# Motor_Driver.net
KiCad netlist of a schematic drawn in Altium Designer
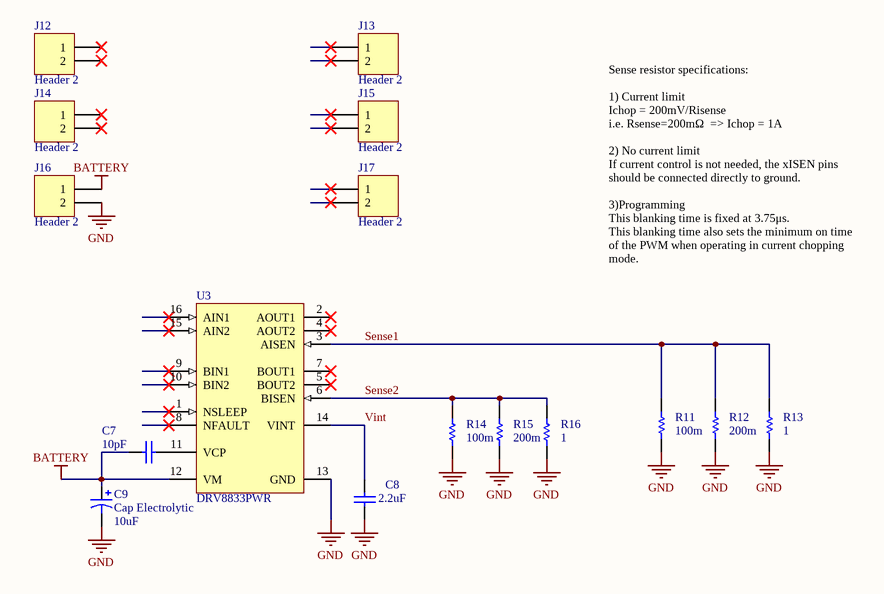
[diagram p0: Motor_Driver.SchDoc]

(export (version "E")
  (design (tool "Eeschema 10.0.6"))
  (components
    (comp (ref "C7")
      (value "10pF")
      (footprint "6-0805_M")
      (description "Capacitor")
      (fields (field (name "Comment") "cap") (field (name "PUBLISHER") "Altium Limited"))
      (libsource (lib "Miscellaneous Devices") (part "Cap"))
    )
    (comp (ref "C8")
      (value "2.2uF")
      (footprint "6-0805_M")
      (description "Capacitor")
      (fields (field (name "Comment") "cap") (field (name "PUBLISHER") "Altium Limited"))
      (libsource (lib "Miscellaneous Devices") (part "Cap"))
    )
    (comp (ref "C9")
      (value "Cap Electrolytic")
      (footprint "capacitor_3d")
      (description "Polarized Capacitor (Radial)")
      (fields (field (name "ALTIUM_VALUE") "10uF") (field (name "PUBLISHER") "Altium Limited"))
      (libsource (lib "Miscellaneous Devices") (part "Cap Pol1"))
    )
    (comp (ref "J12")
      (value "Header 2")
      (footprint "HDR1X2")
      (description "Header, 2-Pin")
      (fields (field (name "PUBLISHER") "Altium Limited"))
      (libsource (lib "") (part "Header 2_1"))
    )
    (comp (ref "J13")
      (value "Header 2")
      (footprint "HDR1X2")
      (description "Header, 2-Pin")
      (fields (field (name "PUBLISHER") "Altium Limited"))
      (libsource (lib "Miscellaneous Connectors") (part "Header 2"))
    )
    (comp (ref "J14")
      (value "Header 2")
      (footprint "HDR1X2")
      (description "Header, 2-Pin")
      (fields (field (name "PUBLISHER") "Altium Limited"))
      (libsource (lib "") (part "Header 2_1"))
    )
    (comp (ref "J15")
      (value "Header 2")
      (footprint "HDR1X2")
      (description "Header, 2-Pin")
      (fields (field (name "PUBLISHER") "Altium Limited"))
      (libsource (lib "Miscellaneous Connectors") (part "Header 2"))
    )
    (comp (ref "J16")
      (value "Header 2")
      (footprint "HDR1X2")
      (description "Header, 2-Pin")
      (fields (field (name "PUBLISHER") "Altium Limited"))
      (libsource (lib "") (part "Header 2_1"))
    )
    (comp (ref "J17")
      (value "Header 2")
      (footprint "HDR1X2")
      (description "Header, 2-Pin")
      (fields (field (name "PUBLISHER") "Altium Limited"))
      (libsource (lib "Miscellaneous Connectors") (part "Header 2"))
    )
    (comp (ref "R11")
      (value "100m")
      (footprint "6-0805_M")
      (description "Resistor")
      (fields (field (name "Comment") "Res1") (field (name "PUBLISHER") "Altium Limited"))
      (libsource (lib "Miscellaneous Devices") (part "Res1"))
    )
    (comp (ref "R12")
      (value "200m")
      (footprint "6-0805_M")
      (description "Resistor")
      (fields (field (name "Comment") "Res1") (field (name "PUBLISHER") "Altium Limited"))
      (libsource (lib "Miscellaneous Devices") (part "Res1"))
    )
    (comp (ref "R13")
      (value "1")
      (footprint "6-0805_M")
      (description "Resistor")
      (fields (field (name "Comment") "Res1") (field (name "PUBLISHER") "Altium Limited"))
      (libsource (lib "Miscellaneous Devices") (part "Res1"))
    )
    (comp (ref "R14")
      (value "100m")
      (footprint "6-0805_M")
      (description "Resistor")
      (fields (field (name "Comment") "Res1") (field (name "PUBLISHER") "Altium Limited"))
      (libsource (lib "Miscellaneous Devices") (part "Res1"))
    )
    (comp (ref "R15")
      (value "200m")
      (footprint "6-0805_M")
      (description "Resistor")
      (fields (field (name "Comment") "Res1") (field (name "PUBLISHER") "Altium Limited"))
      (libsource (lib "Miscellaneous Devices") (part "Res1"))
    )
    (comp (ref "R16")
      (value "1")
      (footprint "6-0805_M")
      (description "Resistor")
      (fields (field (name "Comment") "Res1") (field (name "PUBLISHER") "Altium Limited"))
      (libsource (lib "Miscellaneous Devices") (part "Res1"))
    )
    (comp (ref "U3")
      (value "DRV8833PWR")
      (footprint "TI-PW16_M")
      (fields (field (name "MANUFACTURER") "Texas Instruments"))
      (libsource (lib "Altium Content Vault") (part "CMP-1529-00001-1"))
    )
  )
  (nets
    (net (code "1") (name "/Sense1") (class "Default")
      (node (ref "R11") (pin "2") (pinfunction "2_2") (pintype "passive"))
      (node (ref "R12") (pin "2") (pinfunction "2_2") (pintype "passive"))
      (node (ref "R13") (pin "2") (pinfunction "2_2") (pintype "passive"))
      (node (ref "U3") (pin "3") (pinfunction "AISEN_3") (pintype "input"))
    )
    (net (code "2") (name "/Sense2") (class "Default")
      (node (ref "R14") (pin "2") (pinfunction "2_2") (pintype "passive"))
      (node (ref "R15") (pin "2") (pinfunction "2_2") (pintype "passive"))
      (node (ref "R16") (pin "2") (pinfunction "2_2") (pintype "passive"))
      (node (ref "U3") (pin "6") (pinfunction "BISEN_6") (pintype "input"))
    )
    (net (code "3") (name "/Vint") (class "Default")
      (node (ref "C8") (pin "2") (pinfunction "2_2") (pintype "passive"))
      (node (ref "U3") (pin "14") (pinfunction "VINT_14") (pintype "passive"))
    )
    (net (code "4") (name "BATTERY") (class "Default")
      (node (ref "C7") (pin "2") (pinfunction "2_2") (pintype "passive"))
      (node (ref "C9") (pin "1") (pinfunction "1_1") (pintype "passive"))
      (node (ref "J16") (pin "1") (pinfunction "1_1") (pintype "passive"))
      (node (ref "U3") (pin "12") (pinfunction "VM_12") (pintype "power_in"))
    )
    (net (code "5") (name "GND") (class "Default")
      (node (ref "C8") (pin "1") (pinfunction "1_1") (pintype "passive"))
      (node (ref "C9") (pin "2") (pinfunction "2_2") (pintype "passive"))
      (node (ref "J16") (pin "2") (pinfunction "2_2") (pintype "passive"))
      (node (ref "R11") (pin "1") (pinfunction "1_1") (pintype "passive"))
      (node (ref "R12") (pin "1") (pinfunction "1_1") (pintype "passive"))
      (node (ref "R13") (pin "1") (pinfunction "1_1") (pintype "passive"))
      (node (ref "R14") (pin "1") (pinfunction "1_1") (pintype "passive"))
      (node (ref "R15") (pin "1") (pinfunction "1_1") (pintype "passive"))
      (node (ref "R16") (pin "1") (pinfunction "1_1") (pintype "passive"))
      (node (ref "U3") (pin "13") (pinfunction "GND_13") (pintype "power_in"))
    )
    (net (code "6") (name "Net-(U3-VCP)") (class "Default")
      (node (ref "C7") (pin "1") (pinfunction "1_1") (pintype "passive"))
      (node (ref "U3") (pin "11") (pinfunction "VCP_11") (pintype "passive"))
    )
    (net (code "7") (name "unconnected-(J12-Pad1)") (class "Default")
      (node (ref "J12") (pin "1") (pinfunction "1_1") (pintype "passive+no_connect"))
    )
    (net (code "8") (name "unconnected-(J12-Pad2)") (class "Default")
      (node (ref "J12") (pin "2") (pinfunction "2_2") (pintype "passive+no_connect"))
    )
    (net (code "9") (name "unconnected-(J13-Pad1)") (class "Default")
      (node (ref "J13") (pin "1") (pinfunction "1_1") (pintype "passive+no_connect"))
    )
    (net (code "10") (name "unconnected-(J13-Pad2)") (class "Default")
      (node (ref "J13") (pin "2") (pinfunction "2_2") (pintype "passive+no_connect"))
    )
    (net (code "11") (name "unconnected-(J14-Pad1)") (class "Default")
      (node (ref "J14") (pin "1") (pinfunction "1_1") (pintype "passive+no_connect"))
    )
    (net (code "12") (name "unconnected-(J14-Pad2)") (class "Default")
      (node (ref "J14") (pin "2") (pinfunction "2_2") (pintype "passive+no_connect"))
    )
    (net (code "13") (name "unconnected-(J15-Pad1)") (class "Default")
      (node (ref "J15") (pin "1") (pinfunction "1_1") (pintype "passive+no_connect"))
    )
    (net (code "14") (name "unconnected-(J15-Pad2)") (class "Default")
      (node (ref "J15") (pin "2") (pinfunction "2_2") (pintype "passive+no_connect"))
    )
    (net (code "15") (name "unconnected-(J17-Pad1)") (class "Default")
      (node (ref "J17") (pin "1") (pinfunction "1_1") (pintype "passive+no_connect"))
    )
    (net (code "16") (name "unconnected-(J17-Pad2)") (class "Default")
      (node (ref "J17") (pin "2") (pinfunction "2_2") (pintype "passive+no_connect"))
    )
    (net (code "17") (name "unconnected-(U3-AIN1-Pad16)") (class "Default")
      (node (ref "U3") (pin "16") (pinfunction "AIN1_16") (pintype "input+no_connect"))
    )
    (net (code "18") (name "unconnected-(U3-AIN2-Pad15)") (class "Default")
      (node (ref "U3") (pin "15") (pinfunction "AIN2_15") (pintype "input+no_connect"))
    )
    (net (code "19") (name "unconnected-(U3-AOUT1-Pad2)") (class "Default")
      (node (ref "U3") (pin "2") (pinfunction "AOUT1_2") (pintype "tri_state+no_connect"))
    )
    (net (code "20") (name "unconnected-(U3-AOUT2-Pad4)") (class "Default")
      (node (ref "U3") (pin "4") (pinfunction "AOUT2_4") (pintype "tri_state+no_connect"))
    )
    (net (code "21") (name "unconnected-(U3-BIN1-Pad9)") (class "Default")
      (node (ref "U3") (pin "9") (pinfunction "BIN1_9") (pintype "input+no_connect"))
    )
    (net (code "22") (name "unconnected-(U3-BIN2-Pad10)") (class "Default")
      (node (ref "U3") (pin "10") (pinfunction "BIN2_10") (pintype "input+no_connect"))
    )
    (net (code "23") (name "unconnected-(U3-BOUT1-Pad7)") (class "Default")
      (node (ref "U3") (pin "7") (pinfunction "BOUT1_7") (pintype "tri_state+no_connect"))
    )
    (net (code "24") (name "unconnected-(U3-BOUT2-Pad5)") (class "Default")
      (node (ref "U3") (pin "5") (pinfunction "BOUT2_5") (pintype "tri_state+no_connect"))
    )
    (net (code "25") (name "unconnected-(U3-NFAULT-Pad8)") (class "Default")
      (node (ref "U3") (pin "8") (pinfunction "NFAULT_8") (pintype "open_collector+no_connect"))
    )
    (net (code "26") (name "unconnected-(U3-NSLEEP-Pad1)") (class "Default")
      (node (ref "U3") (pin "1") (pinfunction "NSLEEP_1") (pintype "input+no_connect"))
    )
  )
)
